# 5_6165557048126742241.net
KiCad netlist of a schematic drawn in Altium Designer
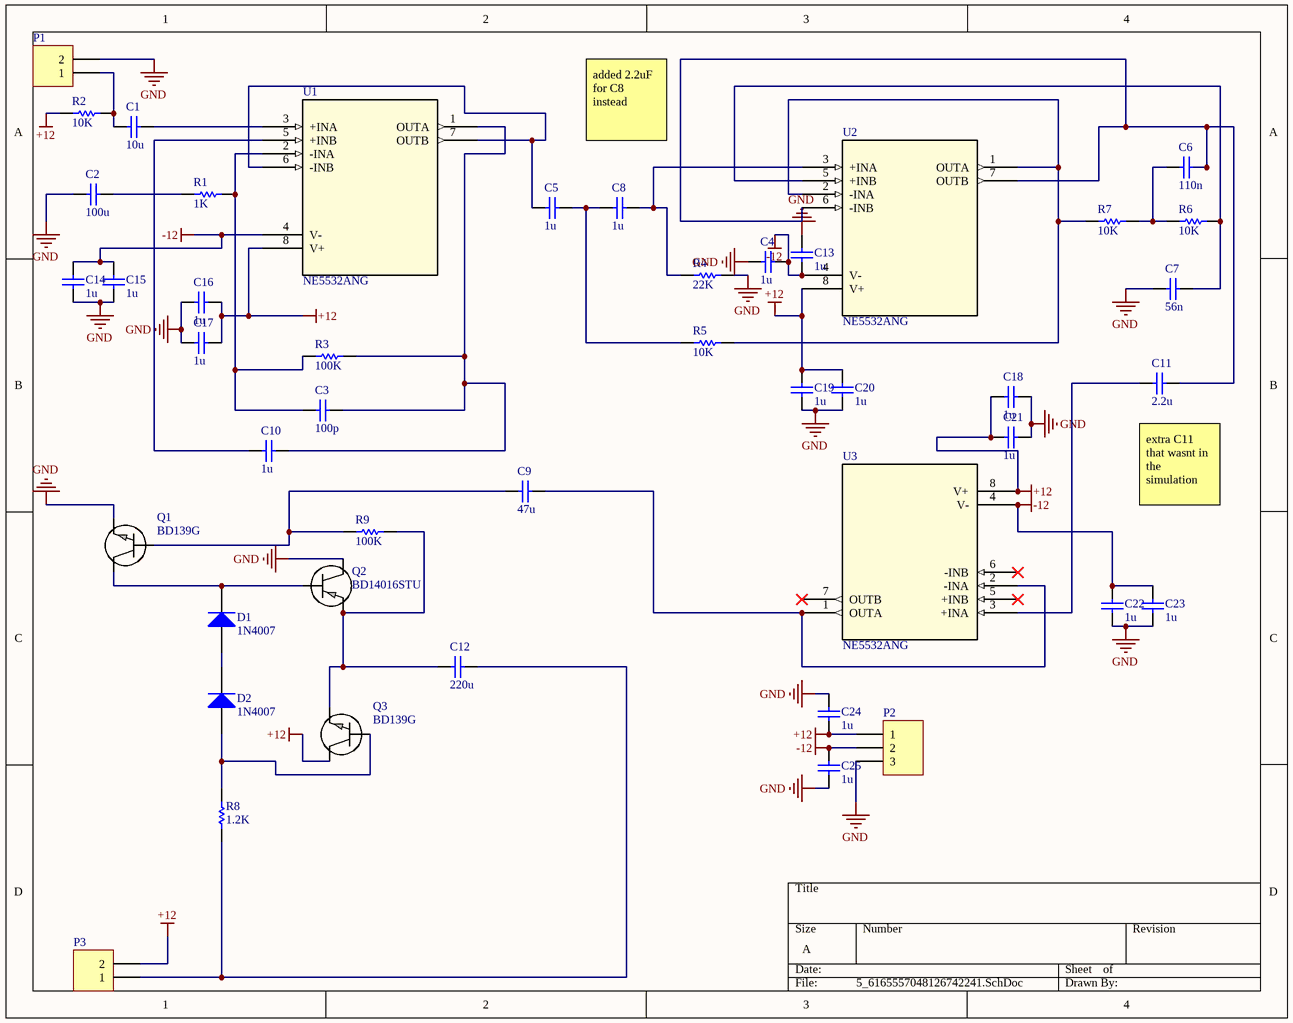
[diagram p0: 5_6165557048126742241.SchDoc]

(export (version "E")
  (design (tool "Eeschema 10.0.6"))
  (components
    (comp (ref "C1")
      (value "10u")
      (footprint "CAP_RDE5C1H104J2K1H03B")
      (description "Capacitor")
      (libsource (lib "Simulation Generic Components") (part "Capacitor"))
    )
    (comp (ref "C2")
      (value "100u")
      (footprint "CAP_RDE5C1H104J2K1H03B")
      (description "Capacitor")
      (libsource (lib "Simulation Generic Components") (part "Capacitor"))
    )
    (comp (ref "C3")
      (value "100p")
      (footprint "CAP_RDE5C1H104J2K1H03B")
      (description "Capacitor")
      (libsource (lib "Simulation Generic Components") (part "Capacitor"))
    )
    (comp (ref "C4")
      (value "1u")
      (footprint "CAP_RDE5C1H104J2K1H03B")
      (description "Capacitor")
      (libsource (lib "Simulation Generic Components") (part "Capacitor"))
    )
    (comp (ref "C5")
      (value "1u")
      (footprint "CAP_RDE5C1H104J2K1H03B")
      (description "Capacitor")
      (libsource (lib "Simulation Generic Components") (part "Capacitor"))
    )
    (comp (ref "C6")
      (value "110n")
      (footprint "CAP_RDE5C1H104J2K1H03B")
      (description "Capacitor")
      (libsource (lib "Simulation Generic Components") (part "Capacitor"))
    )
    (comp (ref "C7")
      (value "56n")
      (footprint "CAP_RDE5C1H104J2K1H03B")
      (description "Capacitor")
      (libsource (lib "Simulation Generic Components") (part "Capacitor"))
    )
    (comp (ref "C8")
      (value "1u")
      (footprint "CAP_RDE5C1H104J2K1H03B")
      (description "Capacitor")
      (libsource (lib "Simulation Generic Components") (part "Capacitor"))
    )
    (comp (ref "C9")
      (value "47u")
      (footprint "CAP_RDE5C1H104J2K1H03B")
      (description "Capacitor")
      (libsource (lib "Simulation Generic Components") (part "Capacitor"))
    )
    (comp (ref "C10")
      (value "1u")
      (footprint "CAP_RDE5C1H104J2K1H03B")
      (description "Capacitor")
      (libsource (lib "Simulation Generic Components") (part "Capacitor"))
    )
    (comp (ref "C11")
      (value "2.2u")
      (footprint "CAP_RDE5C1H104J2K1H03B")
      (description "Capacitor")
      (libsource (lib "Simulation Generic Components") (part "Capacitor"))
    )
    (comp (ref "C12")
      (value "220u")
      (footprint "CAP_RDE5C1H104J2K1H03B")
      (description "Capacitor")
      (libsource (lib "Simulation Generic Components") (part "Capacitor"))
    )
    (comp (ref "C13")
      (value "1u")
      (footprint "CAP_RDE5C1H104J2K1H03B")
      (description "Capacitor")
      (libsource (lib "Simulation Generic Components") (part "Capacitor"))
    )
    (comp (ref "C14")
      (value "1u")
      (footprint "CAP_RDE5C1H104J2K1H03B")
      (description "Capacitor")
      (libsource (lib "Simulation Generic Components") (part "Capacitor"))
    )
    (comp (ref "C15")
      (value "1u")
      (footprint "CAP_RDE5C1H104J2K1H03B")
      (description "Capacitor")
      (libsource (lib "Simulation Generic Components") (part "Capacitor"))
    )
    (comp (ref "C16")
      (value "1u")
      (footprint "CAP_RDE5C1H104J2K1H03B")
      (description "Capacitor")
      (libsource (lib "Simulation Generic Components") (part "Capacitor"))
    )
    (comp (ref "C17")
      (value "1u")
      (footprint "CAP_RDE5C1H104J2K1H03B")
      (description "Capacitor")
      (libsource (lib "Simulation Generic Components") (part "Capacitor"))
    )
    (comp (ref "C18")
      (value "1u")
      (footprint "CAP_RDE5C1H104J2K1H03B")
      (description "Capacitor")
      (libsource (lib "Simulation Generic Components") (part "Capacitor"))
    )
    (comp (ref "C19")
      (value "1u")
      (footprint "CAP_RDE5C1H104J2K1H03B")
      (description "Capacitor")
      (libsource (lib "Simulation Generic Components") (part "Capacitor"))
    )
    (comp (ref "C20")
      (value "1u")
      (footprint "CAP_RDE5C1H104J2K1H03B")
      (description "Capacitor")
      (libsource (lib "Simulation Generic Components") (part "Capacitor"))
    )
    (comp (ref "C21")
      (value "1u")
      (footprint "CAP_RDE5C1H104J2K1H03B")
      (description "Capacitor")
      (libsource (lib "Simulation Generic Components") (part "Capacitor"))
    )
    (comp (ref "C22")
      (value "1u")
      (footprint "CAP_RDE5C1H104J2K1H03B")
      (description "Capacitor")
      (libsource (lib "Simulation Generic Components") (part "Capacitor"))
    )
    (comp (ref "C23")
      (value "1u")
      (footprint "CAP_RDE5C1H104J2K1H03B")
      (description "Capacitor")
      (libsource (lib "Simulation Generic Components") (part "Capacitor"))
    )
    (comp (ref "C24")
      (value "1u")
      (footprint "CAP_RDE5C1H104J2K1H03B")
      (description "Capacitor")
      (libsource (lib "Simulation Generic Components") (part "Capacitor"))
    )
    (comp (ref "C25")
      (value "1u")
      (footprint "CAP_RDE5C1H104J2K1H03B")
      (description "Capacitor")
      (libsource (lib "Simulation Generic Components") (part "Capacitor"))
    )
    (comp (ref "D1")
      (value "1N4007")
      (footprint "My_DO41")
      (description "1 Amp Diode")
      (fields (field (name "ASID PART NUMBER") "1n4007-AS"))
      (libsource (lib "Mylib+Rev+4") (part "1N4007"))
    )
    (comp (ref "D2")
      (value "1N4007")
      (footprint "My_DO41")
      (description "1 Amp Diode")
      (fields (field (name "ASID PART NUMBER") "1n4007-AS"))
      (libsource (lib "Mylib+Rev+4") (part "1N4007"))
    )
    (comp (ref "P1")
      (value "Header 2")
      (footprint "My_1X02")
      (description "Header, 2-Pin")
      (fields (field (name "ASID PART NUMBER") "Header 2-AS"))
      (libsource (lib "Mylib+Rev+4") (part "Header 2"))
    )
    (comp (ref "P2")
      (value "Header 3")
      (footprint "My_CN3")
      (description "Header, 3-Pin")
      (fields (field (name "ASID PART NUMBER") "Header 3-AS"))
      (libsource (lib "Mylib+Rev+4") (part "Header 3"))
    )
    (comp (ref "P3")
      (value "Header 2")
      (footprint "My_1X02")
      (description "Header, 2-Pin")
      (fields (field (name "ASID PART NUMBER") "Header 2-AS"))
      (libsource (lib "Mylib+Rev+4") (part "Header 2"))
    )
    (comp (ref "Q1")
      (value "BD139G")
      (footprint "SOT-32_STM")
      (description "No Description Available")
      (fields (field (name "COPYRIGHT") "Copyright (C) 2026 Ultra Librarian. All rights reserved."))
      (libsource (lib "BD139G") (part "BD139G"))
    )
    (comp (ref "Q2")
      (value "BD14016STU")
      (footprint "SOT-32_STM")
      (description "No Description Available")
      (fields (field (name "COPYRIGHT") "Copyright (C) 2026 Ultra Librarian. All rights reserved."))
      (libsource (lib "BD14016STU") (part "BD14016STU"))
    )
    (comp (ref "Q3")
      (value "BD139G")
      (footprint "SOT-32_STM")
      (description "No Description Available")
      (fields (field (name "COPYRIGHT") "Copyright (C) 2026 Ultra Librarian. All rights reserved."))
      (libsource (lib "BD139G") (part "BD139G"))
    )
    (comp (ref "R1")
      (value "1K")
      (footprint "RESAD700W45L350D185")
      (description "Resistor")
      (libsource (lib "Simulation Generic Components") (part "Resistor"))
    )
    (comp (ref "R2")
      (value "10K")
      (footprint "RESAD700W45L350D185")
      (description "Resistor")
      (libsource (lib "Simulation Generic Components") (part "Resistor"))
    )
    (comp (ref "R3")
      (value "100K")
      (footprint "RESAD700W45L350D185")
      (description "Resistor")
      (libsource (lib "Simulation Generic Components") (part "Resistor"))
    )
    (comp (ref "R4")
      (value "22K")
      (footprint "RESAD700W45L350D185")
      (description "Resistor")
      (libsource (lib "Simulation Generic Components") (part "Resistor"))
    )
    (comp (ref "R5")
      (value "10K")
      (footprint "RESAD700W45L350D185")
      (description "Resistor")
      (libsource (lib "Simulation Generic Components") (part "Resistor"))
    )
    (comp (ref "R6")
      (value "10K")
      (footprint "RESAD700W45L350D185")
      (description "Resistor")
      (libsource (lib "Simulation Generic Components") (part "Resistor"))
    )
    (comp (ref "R7")
      (value "10K")
      (footprint "RESAD700W45L350D185")
      (description "Resistor")
      (libsource (lib "Simulation Generic Components") (part "Resistor"))
    )
    (comp (ref "R8")
      (value "1.2K")
      (footprint "RESAD700W45L350D185")
      (description "Resistor")
      (libsource (lib "Simulation Generic Components") (part "Resistor"))
    )
    (comp (ref "R9")
      (value "100K")
      (footprint "RESAD700W45L350D185")
      (description "Resistor")
      (libsource (lib "Simulation Generic Components") (part "Resistor"))
    )
    (comp (ref "U1")
      (value "NE5532ANG")
      (footprint "P8")
      (description "No Description Available")
      (fields (field (name "COPYRIGHT") "Copyright (C) 2026 Ultra Librarian. All rights reserved."))
      (libsource (lib "") (part "NE5532ANG_1"))
    )
    (comp (ref "U2")
      (value "NE5532ANG")
      (footprint "P8")
      (description "No Description Available")
      (fields (field (name "COPYRIGHT") "Copyright (C) 2026 Ultra Librarian. All rights reserved."))
      (libsource (lib "") (part "NE5532ANG_1"))
    )
    (comp (ref "U3")
      (value "NE5532ANG")
      (footprint "P8")
      (description "No Description Available")
      (fields (field (name "COPYRIGHT") "Copyright (C) 2026 Ultra Librarian. All rights reserved."))
      (libsource (lib "NE5532ANG") (part "NE5532ANG"))
    )
  )
  (nets
    (net (code "1") (name "+12") (class "Default")
      (node (ref "C16") (pin "2") (pinfunction "2_2") (pintype "passive"))
      (node (ref "C17") (pin "2") (pinfunction "2_2") (pintype "passive"))
      (node (ref "C18") (pin "2") (pinfunction "2_2") (pintype "passive"))
      (node (ref "C19") (pin "2") (pinfunction "2_2") (pintype "passive"))
      (node (ref "C20") (pin "2") (pinfunction "2_2") (pintype "passive"))
      (node (ref "C21") (pin "2") (pinfunction "2_2") (pintype "passive"))
      (node (ref "C24") (pin "1") (pinfunction "1_1") (pintype "passive"))
      (node (ref "P2") (pin "1") (pinfunction "1_1") (pintype "passive"))
      (node (ref "P3") (pin "2") (pinfunction "2_2") (pintype "passive"))
      (node (ref "Q3") (pin "2") (pinfunction "C_2") (pintype "passive"))
      (node (ref "R2") (pin "1") (pinfunction "1_1") (pintype "passive"))
      (node (ref "U1") (pin "8") (pinfunction "V+_8") (pintype "power_in"))
      (node (ref "U2") (pin "8") (pinfunction "V+_8") (pintype "power_in"))
      (node (ref "U3") (pin "8") (pinfunction "V+_8") (pintype "power_in"))
    )
    (net (code "2") (name "-12") (class "Default")
      (node (ref "C13") (pin "1") (pinfunction "1_1") (pintype "passive"))
      (node (ref "C14") (pin "2") (pinfunction "2_2") (pintype "passive"))
      (node (ref "C15") (pin "2") (pinfunction "2_2") (pintype "passive"))
      (node (ref "C22") (pin "2") (pinfunction "2_2") (pintype "passive"))
      (node (ref "C23") (pin "2") (pinfunction "2_2") (pintype "passive"))
      (node (ref "C25") (pin "2") (pinfunction "2_2") (pintype "passive"))
      (node (ref "C4") (pin "1") (pinfunction "1_1") (pintype "passive"))
      (node (ref "P2") (pin "2") (pinfunction "2_2") (pintype "passive"))
      (node (ref "U1") (pin "4") (pinfunction "V-_4") (pintype "power_in"))
      (node (ref "U2") (pin "4") (pinfunction "V-_4") (pintype "power_in"))
      (node (ref "U3") (pin "4") (pinfunction "V-_4") (pintype "power_in"))
    )
    (net (code "3") (name "GND") (class "Default")
      (node (ref "C13") (pin "2") (pinfunction "2_2") (pintype "passive"))
      (node (ref "C14") (pin "1") (pinfunction "1_1") (pintype "passive"))
      (node (ref "C15") (pin "1") (pinfunction "1_1") (pintype "passive"))
      (node (ref "C16") (pin "1") (pinfunction "1_1") (pintype "passive"))
      (node (ref "C17") (pin "1") (pinfunction "1_1") (pintype "passive"))
      (node (ref "C18") (pin "1") (pinfunction "1_1") (pintype "passive"))
      (node (ref "C19") (pin "1") (pinfunction "1_1") (pintype "passive"))
      (node (ref "C2") (pin "1") (pinfunction "1_1") (pintype "passive"))
      (node (ref "C20") (pin "1") (pinfunction "1_1") (pintype "passive"))
      (node (ref "C21") (pin "1") (pinfunction "1_1") (pintype "passive"))
      (node (ref "C22") (pin "1") (pinfunction "1_1") (pintype "passive"))
      (node (ref "C23") (pin "1") (pinfunction "1_1") (pintype "passive"))
      (node (ref "C24") (pin "2") (pinfunction "2_2") (pintype "passive"))
      (node (ref "C25") (pin "1") (pinfunction "1_1") (pintype "passive"))
      (node (ref "C4") (pin "2") (pinfunction "2_2") (pintype "passive"))
      (node (ref "C7") (pin "1") (pinfunction "1_1") (pintype "passive"))
      (node (ref "P1") (pin "2") (pinfunction "2_2") (pintype "passive"))
      (node (ref "P2") (pin "3") (pinfunction "3_3") (pintype "passive"))
      (node (ref "Q1") (pin "1") (pinfunction "E_1") (pintype "passive"))
      (node (ref "Q2") (pin "2") (pinfunction "C_2") (pintype "passive"))
      (node (ref "R4") (pin "2") (pinfunction "2_2") (pintype "passive"))
    )
    (net (code "4") (name "Net-(C1-Pad1)") (class "Default")
      (node (ref "C1") (pin "1") (pinfunction "1_1") (pintype "passive"))
      (node (ref "P1") (pin "1") (pinfunction "1_1") (pintype "passive"))
      (node (ref "R2") (pin "2") (pinfunction "2_2") (pintype "passive"))
    )
    (net (code "5") (name "Net-(C2-Pad2)") (class "Default")
      (node (ref "C2") (pin "2") (pinfunction "2_2") (pintype "passive"))
      (node (ref "R1") (pin "1") (pinfunction "1_1") (pintype "passive"))
    )
    (net (code "6") (name "Net-(C5-Pad2)") (class "Default")
      (node (ref "C5") (pin "2") (pinfunction "2_2") (pintype "passive"))
      (node (ref "C8") (pin "1") (pinfunction "1_1") (pintype "passive"))
      (node (ref "R5") (pin "1") (pinfunction "1_1") (pintype "passive"))
    )
    (net (code "7") (name "Net-(C6-Pad1)") (class "Default")
      (node (ref "C6") (pin "1") (pinfunction "1_1") (pintype "passive"))
      (node (ref "R6") (pin "1") (pinfunction "1_1") (pintype "passive"))
      (node (ref "R7") (pin "2") (pinfunction "2_2") (pintype "passive"))
    )
    (net (code "8") (name "Net-(C12-Pad2)") (class "Default")
      (node (ref "C12") (pin "2") (pinfunction "2_2") (pintype "passive"))
      (node (ref "P3") (pin "1") (pinfunction "1_1") (pintype "passive"))
      (node (ref "R8") (pin "1") (pinfunction "1_1") (pintype "passive"))
    )
    (net (code "9") (name "Net-(D1-PadA)") (class "Default")
      (node (ref "D1") (pin "A") (pinfunction "A_A") (pintype "passive"))
      (node (ref "D2") (pin "K") (pinfunction "K_K") (pintype "passive"))
    )
    (net (code "10") (name "Net-(Q1-B)") (class "Default")
      (node (ref "C9") (pin "1") (pinfunction "1_1") (pintype "passive"))
      (node (ref "Q1") (pin "3") (pinfunction "B_3") (pintype "passive"))
      (node (ref "R9") (pin "1") (pinfunction "1_1") (pintype "passive"))
    )
    (net (code "11") (name "Net-(Q1-C)") (class "Default")
      (node (ref "D1") (pin "K") (pinfunction "K_K") (pintype "passive"))
      (node (ref "Q1") (pin "2") (pinfunction "C_2") (pintype "passive"))
      (node (ref "Q2") (pin "3") (pinfunction "B_3") (pintype "passive"))
    )
    (net (code "12") (name "Net-(Q2-E)") (class "Default")
      (node (ref "C12") (pin "1") (pinfunction "1_1") (pintype "passive"))
      (node (ref "Q2") (pin "1") (pinfunction "E_1") (pintype "passive"))
      (node (ref "Q3") (pin "1") (pinfunction "E_1") (pintype "passive"))
      (node (ref "R9") (pin "2") (pinfunction "2_2") (pintype "passive"))
    )
    (net (code "13") (name "Net-(Q3-B)") (class "Default")
      (node (ref "D2") (pin "A") (pinfunction "A_A") (pintype "passive"))
      (node (ref "Q3") (pin "3") (pinfunction "B_3") (pintype "passive"))
      (node (ref "R8") (pin "2") (pinfunction "2_2") (pintype "passive"))
    )
    (net (code "14") (name "Net-(U1-+INA)") (class "Default")
      (node (ref "C1") (pin "2") (pinfunction "2_2") (pintype "passive"))
      (node (ref "U1") (pin "3") (pinfunction "+INA_3") (pintype "input"))
    )
    (net (code "15") (name "Net-(U1-+INB)") (class "Default")
      (node (ref "C10") (pin "1") (pinfunction "1_1") (pintype "passive"))
      (node (ref "U1") (pin "5") (pinfunction "+INB_5") (pintype "input"))
    )
    (net (code "16") (name "Net-(U1--INA)") (class "Default")
      (node (ref "C3") (pin "1") (pinfunction "1_1") (pintype "passive"))
      (node (ref "R1") (pin "2") (pinfunction "2_2") (pintype "passive"))
      (node (ref "R3") (pin "1") (pinfunction "1_1") (pintype "passive"))
      (node (ref "U1") (pin "2") (pinfunction "-INA_2") (pintype "input"))
    )
    (net (code "17") (name "Net-(U1--INB)") (class "Default")
      (node (ref "C5") (pin "1") (pinfunction "1_1") (pintype "passive"))
      (node (ref "U1") (pin "6") (pinfunction "-INB_6") (pintype "input"))
      (node (ref "U1") (pin "7") (pinfunction "OUTB_7") (pintype "output"))
    )
    (net (code "18") (name "Net-(U1-OUTA)") (class "Default")
      (node (ref "C10") (pin "2") (pinfunction "2_2") (pintype "passive"))
      (node (ref "C3") (pin "2") (pinfunction "2_2") (pintype "passive"))
      (node (ref "R3") (pin "2") (pinfunction "2_2") (pintype "passive"))
      (node (ref "U1") (pin "1") (pinfunction "OUTA_1") (pintype "output"))
    )
    (net (code "19") (name "Net-(U2-+INA)") (class "Default")
      (node (ref "C8") (pin "2") (pinfunction "2_2") (pintype "passive"))
      (node (ref "R4") (pin "1") (pinfunction "1_1") (pintype "passive"))
      (node (ref "U2") (pin "3") (pinfunction "+INA_3") (pintype "input"))
    )
    (net (code "20") (name "Net-(U2-+INB)") (class "Default")
      (node (ref "C7") (pin "2") (pinfunction "2_2") (pintype "passive"))
      (node (ref "R6") (pin "2") (pinfunction "2_2") (pintype "passive"))
      (node (ref "U2") (pin "5") (pinfunction "+INB_5") (pintype "input"))
    )
    (net (code "21") (name "Net-(U2--INA)") (class "Default")
      (node (ref "R5") (pin "2") (pinfunction "2_2") (pintype "passive"))
      (node (ref "R7") (pin "1") (pinfunction "1_1") (pintype "passive"))
      (node (ref "U2") (pin "1") (pinfunction "OUTA_1") (pintype "output"))
      (node (ref "U2") (pin "2") (pinfunction "-INA_2") (pintype "input"))
    )
    (net (code "22") (name "Net-(U2--INB)") (class "Default")
      (node (ref "C11") (pin "2") (pinfunction "2_2") (pintype "passive"))
      (node (ref "C6") (pin "2") (pinfunction "2_2") (pintype "passive"))
      (node (ref "U2") (pin "6") (pinfunction "-INB_6") (pintype "input"))
      (node (ref "U2") (pin "7") (pinfunction "OUTB_7") (pintype "output"))
    )
    (net (code "23") (name "Net-(U3-+INA)") (class "Default")
      (node (ref "C11") (pin "1") (pinfunction "1_1") (pintype "passive"))
      (node (ref "U3") (pin "3") (pinfunction "+INA_3") (pintype "input"))
    )
    (net (code "24") (name "Net-(U3--INA)") (class "Default")
      (node (ref "C9") (pin "2") (pinfunction "2_2") (pintype "passive"))
      (node (ref "U3") (pin "1") (pinfunction "OUTA_1") (pintype "output"))
      (node (ref "U3") (pin "2") (pinfunction "-INA_2") (pintype "input"))
    )
    (net (code "25") (name "unconnected-(U3-+INB-Pad5)") (class "Default")
      (node (ref "U3") (pin "5") (pinfunction "+INB_5") (pintype "input+no_connect"))
    )
    (net (code "26") (name "unconnected-(U3--INB-Pad6)") (class "Default")
      (node (ref "U3") (pin "6") (pinfunction "-INB_6") (pintype "input+no_connect"))
    )
    (net (code "27") (name "unconnected-(U3-OUTB-Pad7)") (class "Default")
      (node (ref "U3") (pin "7") (pinfunction "OUTB_7") (pintype "output+no_connect"))
    )
  )
)
